# LED_Heatsink.net
KiCad netlist of a schematic drawn in Altium Designer
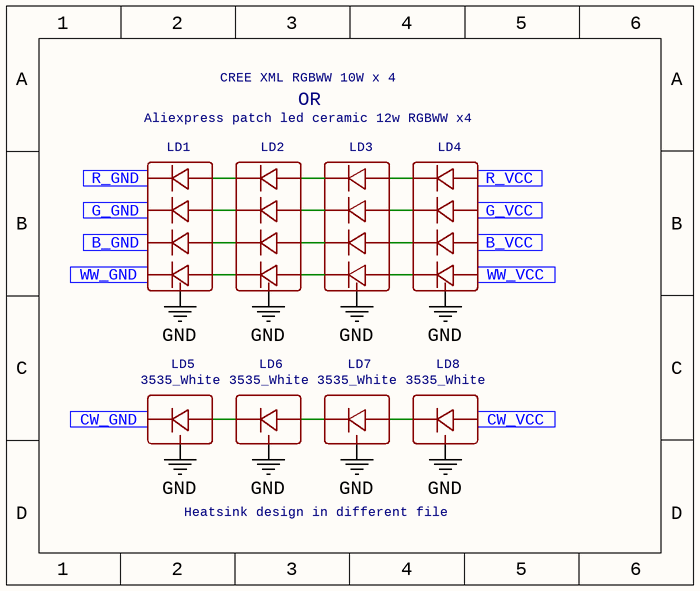
[diagram p0: LED Heatsink.schdoc]

(export (version "E")
  (design (tool "Eeschema 10.0.6"))
  (components
    (comp (ref "LD1")
      (value "CREE XM-L Color Gen 2 High Intensity")
      (fields (field (name "MANUFACTURER") "CREE") (field (name "CONTRIBUTOR") "Gerwin"))
      (libsource (lib "altium-import") (part "root_0_CREE XM-L Color Gen 2 High Intensity_"))
    )
    (comp (ref "LD2")
      (value "CREE XM-L Color Gen 2 High Intensity")
      (fields (field (name "MANUFACTURER") "CREE") (field (name "CONTRIBUTOR") "Gerwin"))
      (libsource (lib "altium-import") (part "root_0_CREE XM-L Color Gen 2 High Intensity_"))
    )
    (comp (ref "LD3")
      (value "CREE XM-L Color Gen 2 High Intensity")
      (fields (field (name "MANUFACTURER") "CREE") (field (name "CONTRIBUTOR") "Gerwin"))
      (libsource (lib "altium-import") (part "root_0_CREE XM-L Color Gen 2 High Intensity_"))
    )
    (comp (ref "LD4")
      (value "CREE XM-L Color Gen 2 High Intensity")
      (fields (field (name "MANUFACTURER") "CREE") (field (name "CONTRIBUTOR") "Gerwin"))
      (libsource (lib "altium-import") (part "root_0_CREE XM-L Color Gen 2 High Intensity_"))
    )
    (comp (ref "LD5")
      (value "3535_White")
      (fields (field (name "CONTRIBUTOR") "hexawiz"))
      (libsource (lib "altium-import") (part "root_0_3535_White_"))
    )
    (comp (ref "LD6")
      (value "3535_White")
      (fields (field (name "CONTRIBUTOR") "hexawiz"))
      (libsource (lib "altium-import") (part "root_0_3535_White_"))
    )
    (comp (ref "LD7")
      (value "3535_White")
      (fields (field (name "CONTRIBUTOR") "hexawiz"))
      (libsource (lib "altium-import") (part "root_0_3535_White_"))
    )
    (comp (ref "LD8")
      (value "3535_White")
      (fields (field (name "CONTRIBUTOR") "hexawiz"))
      (libsource (lib "altium-import") (part "root_0_3535_White_"))
    )
  )
  (nets
    (net (code "1") (name "/B_GND") (class "Default")
      (node (ref "LD1") (pin "6") (pinfunction "6_6") (pintype "passive"))
    )
    (net (code "2") (name "/B_VCC") (class "Default")
      (node (ref "LD4") (pin "3") (pinfunction "3_3") (pintype "passive"))
    )
    (net (code "3") (name "/CW_GND") (class "Default")
      (node (ref "LD5") (pin "1") (pinfunction "1_1") (pintype "passive"))
    )
    (net (code "4") (name "/CW_VCC") (class "Default")
      (node (ref "LD8") (pin "2") (pinfunction "2_2") (pintype "passive"))
    )
    (net (code "5") (name "/G_GND") (class "Default")
      (node (ref "LD1") (pin "7") (pinfunction "7_7") (pintype "passive"))
    )
    (net (code "6") (name "/G_VCC") (class "Default")
      (node (ref "LD4") (pin "2") (pinfunction "2_2") (pintype "passive"))
    )
    (net (code "7") (name "/R_GND") (class "Default")
      (node (ref "LD1") (pin "8") (pinfunction "8_8") (pintype "passive"))
    )
    (net (code "8") (name "/R_VCC") (class "Default")
      (node (ref "LD4") (pin "1") (pinfunction "1_1") (pintype "passive"))
    )
    (net (code "9") (name "/WW_GND") (class "Default")
      (node (ref "LD1") (pin "5") (pinfunction "5_5") (pintype "passive"))
    )
    (net (code "10") (name "/WW_VCC") (class "Default")
      (node (ref "LD4") (pin "4") (pinfunction "4_4") (pintype "passive"))
    )
    (net (code "11") (name "GND") (class "Default")
      (node (ref "LD1") (pin "9") (pinfunction "HS_9") (pintype "passive"))
      (node (ref "LD2") (pin "9") (pinfunction "HS_9") (pintype "passive"))
      (node (ref "LD3") (pin "9") (pinfunction "HS_9") (pintype "passive"))
      (node (ref "LD4") (pin "9") (pinfunction "HS_9") (pintype "passive"))
      (node (ref "LD5") (pin "3") (pinfunction "3_3") (pintype "passive"))
      (node (ref "LD6") (pin "3") (pinfunction "3_3") (pintype "passive"))
      (node (ref "LD7") (pin "3") (pinfunction "3_3") (pintype "passive"))
      (node (ref "LD8") (pin "3") (pinfunction "3_3") (pintype "passive"))
    )
    (net (code "12") (name "Net-(LD1-Pad1)") (class "Default")
      (node (ref "LD1") (pin "1") (pinfunction "1_1") (pintype "passive"))
      (node (ref "LD2") (pin "8") (pinfunction "8_8") (pintype "passive"))
    )
    (net (code "13") (name "Net-(LD1-Pad2)") (class "Default")
      (node (ref "LD1") (pin "2") (pinfunction "2_2") (pintype "passive"))
      (node (ref "LD2") (pin "7") (pinfunction "7_7") (pintype "passive"))
    )
    (net (code "14") (name "Net-(LD1-Pad3)") (class "Default")
      (node (ref "LD1") (pin "3") (pinfunction "3_3") (pintype "passive"))
      (node (ref "LD2") (pin "6") (pinfunction "6_6") (pintype "passive"))
    )
    (net (code "15") (name "Net-(LD1-Pad4)") (class "Default")
      (node (ref "LD1") (pin "4") (pinfunction "4_4") (pintype "passive"))
      (node (ref "LD2") (pin "5") (pinfunction "5_5") (pintype "passive"))
    )
    (net (code "16") (name "Net-(LD2-Pad1)") (class "Default")
      (node (ref "LD2") (pin "1") (pinfunction "1_1") (pintype "passive"))
      (node (ref "LD3") (pin "8") (pinfunction "8_8") (pintype "passive"))
    )
    (net (code "17") (name "Net-(LD2-Pad2)") (class "Default")
      (node (ref "LD2") (pin "2") (pinfunction "2_2") (pintype "passive"))
      (node (ref "LD3") (pin "7") (pinfunction "7_7") (pintype "passive"))
    )
    (net (code "18") (name "Net-(LD2-Pad3)") (class "Default")
      (node (ref "LD2") (pin "3") (pinfunction "3_3") (pintype "passive"))
      (node (ref "LD3") (pin "6") (pinfunction "6_6") (pintype "passive"))
    )
    (net (code "19") (name "Net-(LD2-Pad4)") (class "Default")
      (node (ref "LD2") (pin "4") (pinfunction "4_4") (pintype "passive"))
      (node (ref "LD3") (pin "5") (pinfunction "5_5") (pintype "passive"))
    )
    (net (code "20") (name "Net-(LD3-Pad1)") (class "Default")
      (node (ref "LD3") (pin "1") (pinfunction "1_1") (pintype "passive"))
      (node (ref "LD4") (pin "8") (pinfunction "8_8") (pintype "passive"))
    )
    (net (code "21") (name "Net-(LD3-Pad2)") (class "Default")
      (node (ref "LD3") (pin "2") (pinfunction "2_2") (pintype "passive"))
      (node (ref "LD4") (pin "7") (pinfunction "7_7") (pintype "passive"))
    )
    (net (code "22") (name "Net-(LD3-Pad3)") (class "Default")
      (node (ref "LD3") (pin "3") (pinfunction "3_3") (pintype "passive"))
      (node (ref "LD4") (pin "6") (pinfunction "6_6") (pintype "passive"))
    )
    (net (code "23") (name "Net-(LD3-Pad4)") (class "Default")
      (node (ref "LD3") (pin "4") (pinfunction "4_4") (pintype "passive"))
      (node (ref "LD4") (pin "5") (pinfunction "5_5") (pintype "passive"))
    )
    (net (code "24") (name "Net-(LD5-Pad2)") (class "Default")
      (node (ref "LD5") (pin "2") (pinfunction "2_2") (pintype "passive"))
      (node (ref "LD6") (pin "1") (pinfunction "1_1") (pintype "passive"))
    )
    (net (code "25") (name "Net-(LD6-Pad2)") (class "Default")
      (node (ref "LD6") (pin "2") (pinfunction "2_2") (pintype "passive"))
      (node (ref "LD7") (pin "1") (pinfunction "1_1") (pintype "passive"))
    )
    (net (code "26") (name "Net-(LD7-Pad2)") (class "Default")
      (node (ref "LD7") (pin "2") (pinfunction "2_2") (pintype "passive"))
      (node (ref "LD8") (pin "1") (pinfunction "1_1") (pintype "passive"))
    )
  )
)
